# RHD2164_headstage1.net
KiCad netlist of a schematic drawn in EAGLE
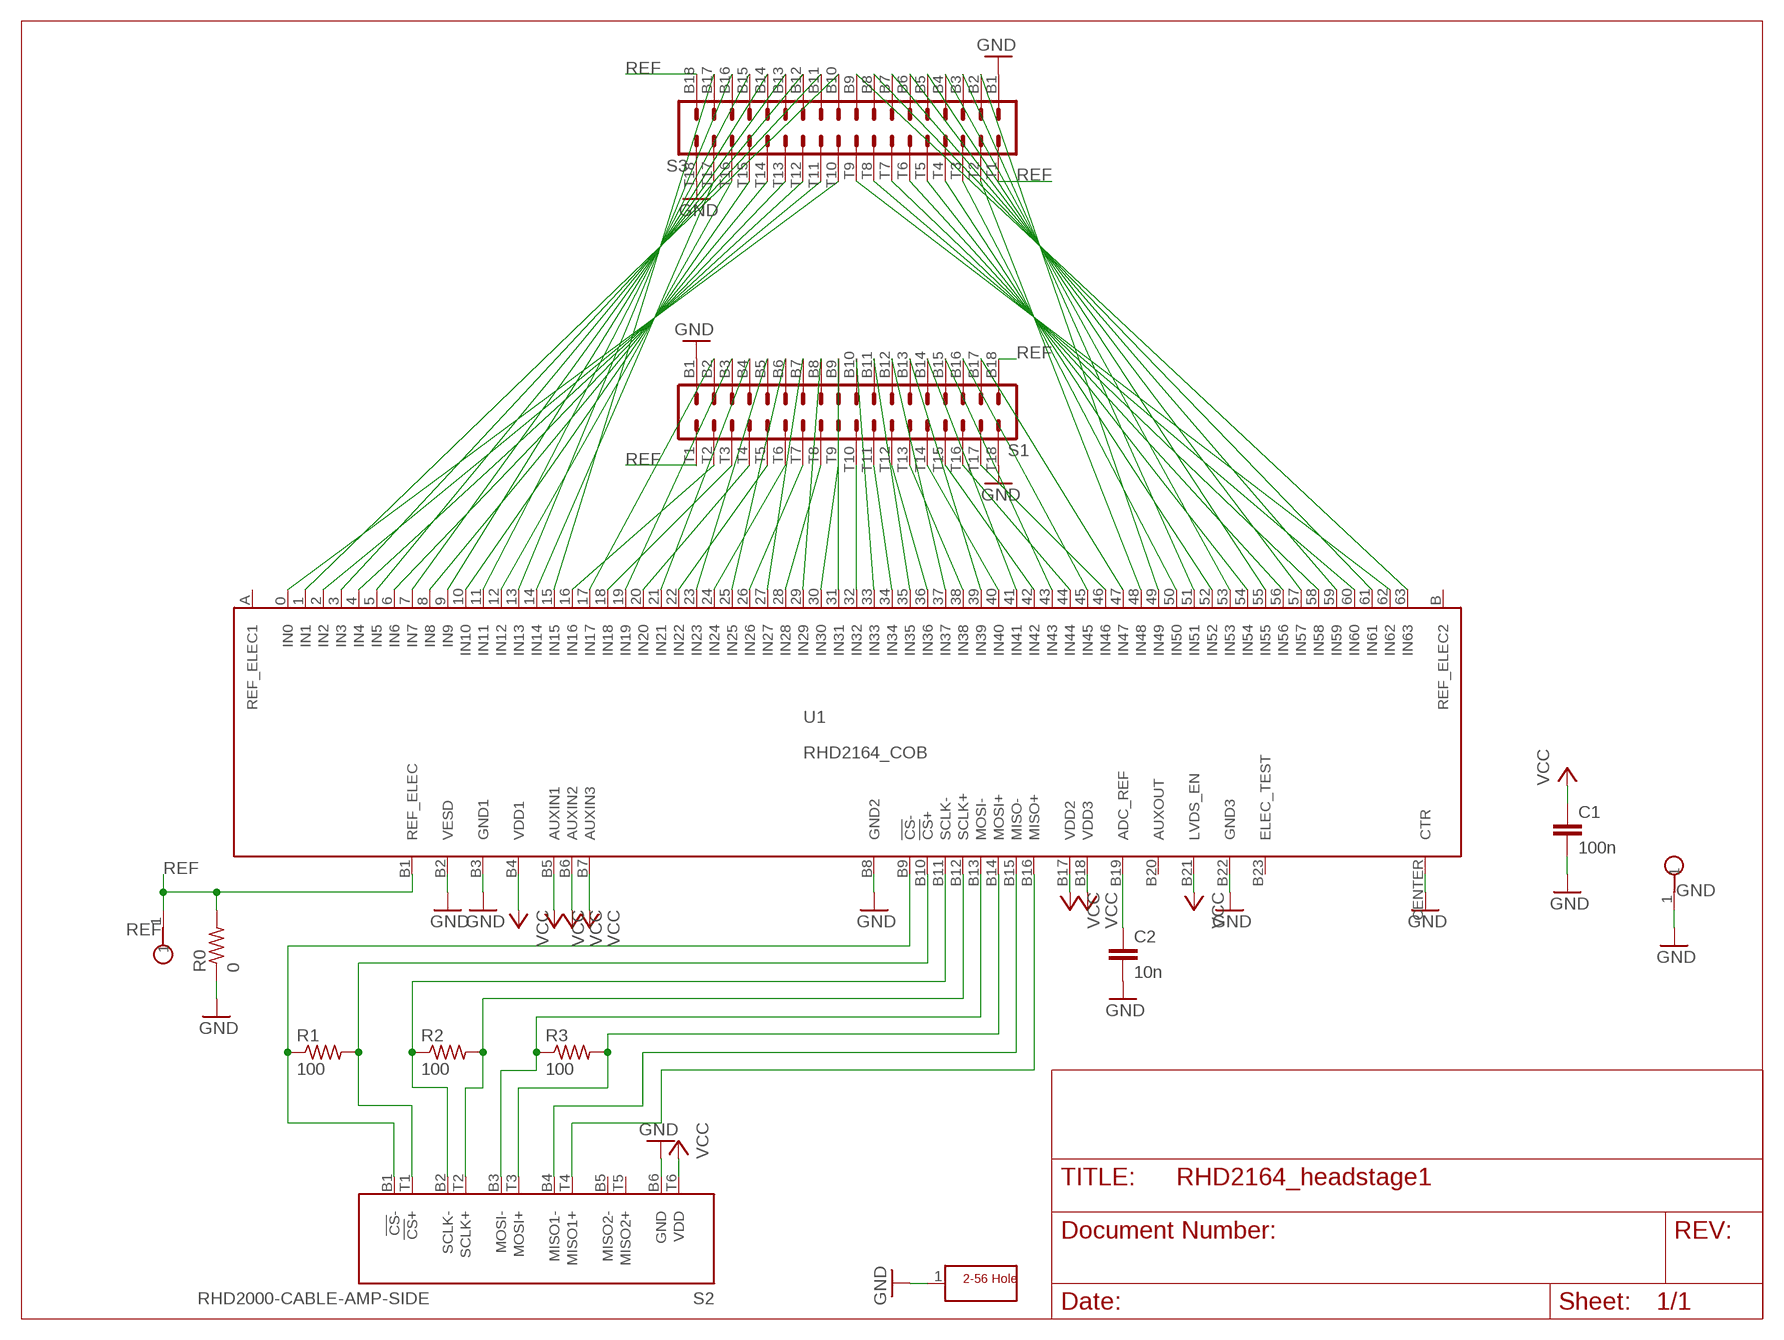
[diagram p0: schematic, sheet 1]

(export (version "E")
  (design (tool "Eeschema 10.0.6"))
  (components
    (comp (ref "C1")
      (value "100n")
      (footprint "eagle-import:0402")
      (libsource (lib "eagle-import") (part "C_0402"))
    )
    (comp (ref "C2")
      (value "10n")
      (footprint "eagle-import:0201")
      (libsource (lib "eagle-import") (part "C_0201"))
    )
    (comp (ref "GND")
      (value "TESTPOINT_SMALL")
      (footprint "eagle-import:TESTPOINT_SMALL")
      (libsource (lib "eagle-import") (part "TESTPOINT_SMALL"))
    )
    (comp (ref "H1")
      (value "SCREW_HOLE_2-56")
      (footprint "eagle-import:SCREW_HOLE_2-56")
      (libsource (lib "eagle-import") (part "SCREW_HOLE_2-56"))
    )
    (comp (ref "R0")
      (value "0")
      (footprint "eagle-import:0402")
      (libsource (lib "eagle-import") (part "R_0402"))
    )
    (comp (ref "R1")
      (value "100")
      (footprint "eagle-import:0201")
      (libsource (lib "eagle-import") (part "R_0201"))
    )
    (comp (ref "R2")
      (value "100")
      (footprint "eagle-import:0201")
      (libsource (lib "eagle-import") (part "R_0201"))
    )
    (comp (ref "R3")
      (value "100")
      (footprint "eagle-import:0201")
      (libsource (lib "eagle-import") (part "R_0201"))
    )
    (comp (ref "REF")
      (value "TESTPOINT_SMALL")
      (footprint "eagle-import:TESTPOINT_SMALL")
      (libsource (lib "eagle-import") (part "TESTPOINT_SMALL"))
    )
    (comp (ref "S1")
      (value "OMNETICS_A79025")
      (footprint "eagle-import:OMNETICS_A79025")
      (libsource (lib "eagle-import") (part "OMNETICS_A79025"))
    )
    (comp (ref "S2")
      (value "RHD2000-CABLE-AMP-SIDE")
      (footprint "eagle-import:OMNETICS_PZN-12-AA")
      (libsource (lib "eagle-import") (part "RHD2000-CABLE-AMP-SIDE"))
    )
    (comp (ref "S3")
      (value "OMNETICS_A79025")
      (footprint "eagle-import:OMNETICS_A79025")
      (libsource (lib "eagle-import") (part "OMNETICS_A79025"))
    )
    (comp (ref "U1")
      (value "RHD2164_COB")
      (footprint "eagle-import:RHD2164_COB")
      (libsource (lib "eagle-import") (part "RHD2164_COB"))
    )
  )
  (nets
    (net (code "1") (name "/REF") (class "Default")
      (node (ref "R0") (pin "2") (pinfunction "2_2") (pintype "passive"))
      (node (ref "REF") (pin "1") (pinfunction "1_1") (pintype "passive"))
      (node (ref "S1") (pin "B18") (pinfunction "B18_B18") (pintype "passive"))
      (node (ref "S1") (pin "T1") (pinfunction "T1_T1") (pintype "passive"))
      (node (ref "S3") (pin "B18") (pinfunction "B18_B18") (pintype "passive"))
      (node (ref "S3") (pin "T1") (pinfunction "T1_T1") (pintype "passive"))
      (node (ref "U1") (pin "B1") (pinfunction "REF_ELEC_B1") (pintype "input"))
    )
    (net (code "2") (name "GND") (class "Default")
      (node (ref "C1") (pin "2") (pinfunction "2_2") (pintype "passive"))
      (node (ref "C2") (pin "2") (pinfunction "2_2") (pintype "passive"))
      (node (ref "GND") (pin "1") (pinfunction "1_1") (pintype "passive"))
      (node (ref "H1") (pin "1") (pinfunction "1_1") (pintype "passive"))
      (node (ref "R0") (pin "1") (pinfunction "1_1") (pintype "passive"))
      (node (ref "S1") (pin "B1") (pinfunction "B1_B1") (pintype "passive"))
      (node (ref "S1") (pin "T18") (pinfunction "T18_T18") (pintype "passive"))
      (node (ref "S2") (pin "B6") (pinfunction "GND_B6") (pintype "power_in"))
      (node (ref "S3") (pin "B1") (pinfunction "B1_B1") (pintype "passive"))
      (node (ref "S3") (pin "T18") (pinfunction "T18_T18") (pintype "passive"))
      (node (ref "U1") (pin "B2") (pinfunction "VESD_B2") (pintype "power_in"))
      (node (ref "U1") (pin "B22") (pinfunction "GND3_B22") (pintype "power_in"))
      (node (ref "U1") (pin "B3") (pinfunction "GND1_B3") (pintype "power_in"))
      (node (ref "U1") (pin "B8") (pinfunction "GND2_B8") (pintype "power_in"))
      (node (ref "U1") (pin "CENTER") (pinfunction "CTR_CENTER") (pintype "power_in"))
    )
    (net (code "3") (name "Net-(S2-MISO1+)") (class "Default")
      (node (ref "S2") (pin "T4") (pinfunction "MISO1+_T4") (pintype "bidirectional"))
      (node (ref "U1") (pin "B16") (pinfunction "MISO+_B16") (pintype "output"))
    )
    (net (code "4") (name "Net-(S2-MISO1-)") (class "Default")
      (node (ref "S2") (pin "B4") (pinfunction "MISO1-_B4") (pintype "bidirectional"))
      (node (ref "U1") (pin "B15") (pinfunction "MISO-_B15") (pintype "output"))
    )
    (net (code "5") (name "Net-(S2-MOSI+)") (class "Default")
      (node (ref "R3") (pin "2") (pinfunction "2_2") (pintype "passive"))
      (node (ref "S2") (pin "T3") (pinfunction "MOSI+_T3") (pintype "bidirectional"))
      (node (ref "U1") (pin "B14") (pinfunction "MOSI+_B14") (pintype "input"))
    )
    (net (code "6") (name "Net-(S2-MOSI-)") (class "Default")
      (node (ref "R3") (pin "1") (pinfunction "1_1") (pintype "passive"))
      (node (ref "S2") (pin "B3") (pinfunction "MOSI-_B3") (pintype "bidirectional"))
      (node (ref "U1") (pin "B13") (pinfunction "MOSI-_B13") (pintype "input"))
    )
    (net (code "7") (name "Net-(S2-SCLK+)") (class "Default")
      (node (ref "R2") (pin "2") (pinfunction "2_2") (pintype "passive"))
      (node (ref "S2") (pin "T2") (pinfunction "SCLK+_T2") (pintype "bidirectional"))
      (node (ref "U1") (pin "B12") (pinfunction "SCLK+_B12") (pintype "input"))
    )
    (net (code "8") (name "Net-(S2-SCLK-)") (class "Default")
      (node (ref "R2") (pin "1") (pinfunction "1_1") (pintype "passive"))
      (node (ref "S2") (pin "B2") (pinfunction "SCLK-_B2") (pintype "bidirectional"))
      (node (ref "U1") (pin "B11") (pinfunction "SCLK-_B11") (pintype "input"))
    )
    (net (code "9") (name "Net-(S2-~{CS}+)") (class "Default")
      (node (ref "R1") (pin "2") (pinfunction "2_2") (pintype "passive"))
      (node (ref "S2") (pin "T1") (pinfunction "~{CS}+_T1") (pintype "bidirectional"))
      (node (ref "U1") (pin "B10") (pinfunction "~{CS}+_B10") (pintype "input"))
    )
    (net (code "10") (name "Net-(S2-~{CS}-)") (class "Default")
      (node (ref "R1") (pin "1") (pinfunction "1_1") (pintype "passive"))
      (node (ref "S2") (pin "B1") (pinfunction "~{CS}-_B1") (pintype "bidirectional"))
      (node (ref "U1") (pin "B9") (pinfunction "~{CS}-_B9") (pintype "input"))
    )
    (net (code "11") (name "Net-(U1-ADC_REF)") (class "Default")
      (node (ref "C2") (pin "1") (pinfunction "1_1") (pintype "passive"))
      (node (ref "U1") (pin "B19") (pinfunction "ADC_REF_B19") (pintype "passive"))
    )
    (net (code "12") (name "Net-(U1-IN0)") (class "Default")
      (node (ref "S3") (pin "T10") (pinfunction "T10_T10") (pintype "passive"))
      (node (ref "U1") (pin "0") (pinfunction "IN0_0") (pintype "input"))
    )
    (net (code "13") (name "Net-(U1-IN1)") (class "Default")
      (node (ref "S3") (pin "B10") (pinfunction "B10_B10") (pintype "passive"))
      (node (ref "U1") (pin "1") (pinfunction "IN1_1") (pintype "input"))
    )
    (net (code "14") (name "Net-(U1-IN2)") (class "Default")
      (node (ref "S3") (pin "T11") (pinfunction "T11_T11") (pintype "passive"))
      (node (ref "U1") (pin "2") (pinfunction "IN2_2") (pintype "input"))
    )
    (net (code "15") (name "Net-(U1-IN3)") (class "Default")
      (node (ref "S3") (pin "B11") (pinfunction "B11_B11") (pintype "passive"))
      (node (ref "U1") (pin "3") (pinfunction "IN3_3") (pintype "input"))
    )
    (net (code "16") (name "Net-(U1-IN4)") (class "Default")
      (node (ref "S3") (pin "T12") (pinfunction "T12_T12") (pintype "passive"))
      (node (ref "U1") (pin "4") (pinfunction "IN4_4") (pintype "input"))
    )
    (net (code "17") (name "Net-(U1-IN5)") (class "Default")
      (node (ref "S3") (pin "B12") (pinfunction "B12_B12") (pintype "passive"))
      (node (ref "U1") (pin "5") (pinfunction "IN5_5") (pintype "input"))
    )
    (net (code "18") (name "Net-(U1-IN6)") (class "Default")
      (node (ref "S3") (pin "T13") (pinfunction "T13_T13") (pintype "passive"))
      (node (ref "U1") (pin "6") (pinfunction "IN6_6") (pintype "input"))
    )
    (net (code "19") (name "Net-(U1-IN7)") (class "Default")
      (node (ref "S3") (pin "B13") (pinfunction "B13_B13") (pintype "passive"))
      (node (ref "U1") (pin "7") (pinfunction "IN7_7") (pintype "input"))
    )
    (net (code "20") (name "Net-(U1-IN8)") (class "Default")
      (node (ref "S3") (pin "T14") (pinfunction "T14_T14") (pintype "passive"))
      (node (ref "U1") (pin "8") (pinfunction "IN8_8") (pintype "input"))
    )
    (net (code "21") (name "Net-(U1-IN9)") (class "Default")
      (node (ref "S3") (pin "B14") (pinfunction "B14_B14") (pintype "passive"))
      (node (ref "U1") (pin "9") (pinfunction "IN9_9") (pintype "input"))
    )
    (net (code "22") (name "Net-(U1-IN10)") (class "Default")
      (node (ref "S3") (pin "T15") (pinfunction "T15_T15") (pintype "passive"))
      (node (ref "U1") (pin "10") (pinfunction "IN10_10") (pintype "input"))
    )
    (net (code "23") (name "Net-(U1-IN11)") (class "Default")
      (node (ref "S3") (pin "B15") (pinfunction "B15_B15") (pintype "passive"))
      (node (ref "U1") (pin "11") (pinfunction "IN11_11") (pintype "input"))
    )
    (net (code "24") (name "Net-(U1-IN12)") (class "Default")
      (node (ref "S3") (pin "T16") (pinfunction "T16_T16") (pintype "passive"))
      (node (ref "U1") (pin "12") (pinfunction "IN12_12") (pintype "input"))
    )
    (net (code "25") (name "Net-(U1-IN13)") (class "Default")
      (node (ref "S3") (pin "B16") (pinfunction "B16_B16") (pintype "passive"))
      (node (ref "U1") (pin "13") (pinfunction "IN13_13") (pintype "input"))
    )
    (net (code "26") (name "Net-(U1-IN14)") (class "Default")
      (node (ref "S3") (pin "T17") (pinfunction "T17_T17") (pintype "passive"))
      (node (ref "U1") (pin "14") (pinfunction "IN14_14") (pintype "input"))
    )
    (net (code "27") (name "Net-(U1-IN15)") (class "Default")
      (node (ref "S3") (pin "B17") (pinfunction "B17_B17") (pintype "passive"))
      (node (ref "U1") (pin "15") (pinfunction "IN15_15") (pintype "input"))
    )
    (net (code "28") (name "Net-(U1-IN16)") (class "Default")
      (node (ref "S1") (pin "T2") (pinfunction "T2_T2") (pintype "passive"))
      (node (ref "U1") (pin "16") (pinfunction "IN16_16") (pintype "input"))
    )
    (net (code "29") (name "Net-(U1-IN17)") (class "Default")
      (node (ref "S1") (pin "B2") (pinfunction "B2_B2") (pintype "passive"))
      (node (ref "U1") (pin "17") (pinfunction "IN17_17") (pintype "input"))
    )
    (net (code "30") (name "Net-(U1-IN18)") (class "Default")
      (node (ref "S1") (pin "T3") (pinfunction "T3_T3") (pintype "passive"))
      (node (ref "U1") (pin "18") (pinfunction "IN18_18") (pintype "input"))
    )
    (net (code "31") (name "Net-(U1-IN19)") (class "Default")
      (node (ref "S1") (pin "B3") (pinfunction "B3_B3") (pintype "passive"))
      (node (ref "U1") (pin "19") (pinfunction "IN19_19") (pintype "input"))
    )
    (net (code "32") (name "Net-(U1-IN20)") (class "Default")
      (node (ref "S1") (pin "T4") (pinfunction "T4_T4") (pintype "passive"))
      (node (ref "U1") (pin "20") (pinfunction "IN20_20") (pintype "input"))
    )
    (net (code "33") (name "Net-(U1-IN21)") (class "Default")
      (node (ref "S1") (pin "B4") (pinfunction "B4_B4") (pintype "passive"))
      (node (ref "U1") (pin "21") (pinfunction "IN21_21") (pintype "input"))
    )
    (net (code "34") (name "Net-(U1-IN22)") (class "Default")
      (node (ref "S1") (pin "T5") (pinfunction "T5_T5") (pintype "passive"))
      (node (ref "U1") (pin "22") (pinfunction "IN22_22") (pintype "input"))
    )
    (net (code "35") (name "Net-(U1-IN23)") (class "Default")
      (node (ref "S1") (pin "B5") (pinfunction "B5_B5") (pintype "passive"))
      (node (ref "U1") (pin "23") (pinfunction "IN23_23") (pintype "input"))
    )
    (net (code "36") (name "Net-(U1-IN24)") (class "Default")
      (node (ref "S1") (pin "T6") (pinfunction "T6_T6") (pintype "passive"))
      (node (ref "U1") (pin "24") (pinfunction "IN24_24") (pintype "input"))
    )
    (net (code "37") (name "Net-(U1-IN25)") (class "Default")
      (node (ref "S1") (pin "B6") (pinfunction "B6_B6") (pintype "passive"))
      (node (ref "U1") (pin "25") (pinfunction "IN25_25") (pintype "input"))
    )
    (net (code "38") (name "Net-(U1-IN26)") (class "Default")
      (node (ref "S1") (pin "T7") (pinfunction "T7_T7") (pintype "passive"))
      (node (ref "U1") (pin "26") (pinfunction "IN26_26") (pintype "input"))
    )
    (net (code "39") (name "Net-(U1-IN27)") (class "Default")
      (node (ref "S1") (pin "B7") (pinfunction "B7_B7") (pintype "passive"))
      (node (ref "U1") (pin "27") (pinfunction "IN27_27") (pintype "input"))
    )
    (net (code "40") (name "Net-(U1-IN28)") (class "Default")
      (node (ref "S1") (pin "T8") (pinfunction "T8_T8") (pintype "passive"))
      (node (ref "U1") (pin "28") (pinfunction "IN28_28") (pintype "input"))
    )
    (net (code "41") (name "Net-(U1-IN29)") (class "Default")
      (node (ref "S1") (pin "B8") (pinfunction "B8_B8") (pintype "passive"))
      (node (ref "U1") (pin "29") (pinfunction "IN29_29") (pintype "input"))
    )
    (net (code "42") (name "Net-(U1-IN30)") (class "Default")
      (node (ref "S1") (pin "T9") (pinfunction "T9_T9") (pintype "passive"))
      (node (ref "U1") (pin "30") (pinfunction "IN30_30") (pintype "input"))
    )
    (net (code "43") (name "Net-(U1-IN31)") (class "Default")
      (node (ref "S1") (pin "B9") (pinfunction "B9_B9") (pintype "passive"))
      (node (ref "U1") (pin "31") (pinfunction "IN31_31") (pintype "input"))
    )
    (net (code "44") (name "Net-(U1-IN32)") (class "Default")
      (node (ref "S1") (pin "T10") (pinfunction "T10_T10") (pintype "passive"))
      (node (ref "U1") (pin "32") (pinfunction "IN32_32") (pintype "input"))
    )
    (net (code "45") (name "Net-(U1-IN33)") (class "Default")
      (node (ref "S1") (pin "B10") (pinfunction "B10_B10") (pintype "passive"))
      (node (ref "U1") (pin "33") (pinfunction "IN33_33") (pintype "input"))
    )
    (net (code "46") (name "Net-(U1-IN34)") (class "Default")
      (node (ref "S1") (pin "T11") (pinfunction "T11_T11") (pintype "passive"))
      (node (ref "U1") (pin "34") (pinfunction "IN34_34") (pintype "input"))
    )
    (net (code "47") (name "Net-(U1-IN35)") (class "Default")
      (node (ref "S1") (pin "B11") (pinfunction "B11_B11") (pintype "passive"))
      (node (ref "U1") (pin "35") (pinfunction "IN35_35") (pintype "input"))
    )
    (net (code "48") (name "Net-(U1-IN36)") (class "Default")
      (node (ref "S1") (pin "T12") (pinfunction "T12_T12") (pintype "passive"))
      (node (ref "U1") (pin "36") (pinfunction "IN36_36") (pintype "input"))
    )
    (net (code "49") (name "Net-(U1-IN37)") (class "Default")
      (node (ref "S1") (pin "B12") (pinfunction "B12_B12") (pintype "passive"))
      (node (ref "U1") (pin "37") (pinfunction "IN37_37") (pintype "input"))
    )
    (net (code "50") (name "Net-(U1-IN38)") (class "Default")
      (node (ref "S1") (pin "T13") (pinfunction "T13_T13") (pintype "passive"))
      (node (ref "U1") (pin "38") (pinfunction "IN38_38") (pintype "input"))
    )
    (net (code "51") (name "Net-(U1-IN39)") (class "Default")
      (node (ref "S1") (pin "B13") (pinfunction "B13_B13") (pintype "passive"))
      (node (ref "U1") (pin "39") (pinfunction "IN39_39") (pintype "input"))
    )
    (net (code "52") (name "Net-(U1-IN40)") (class "Default")
      (node (ref "S1") (pin "T14") (pinfunction "T14_T14") (pintype "passive"))
      (node (ref "U1") (pin "40") (pinfunction "IN40_40") (pintype "input"))
    )
    (net (code "53") (name "Net-(U1-IN41)") (class "Default")
      (node (ref "S1") (pin "B14") (pinfunction "B14_B14") (pintype "passive"))
      (node (ref "U1") (pin "41") (pinfunction "IN41_41") (pintype "input"))
    )
    (net (code "54") (name "Net-(U1-IN42)") (class "Default")
      (node (ref "S1") (pin "T15") (pinfunction "T15_T15") (pintype "passive"))
      (node (ref "U1") (pin "42") (pinfunction "IN42_42") (pintype "input"))
    )
    (net (code "55") (name "Net-(U1-IN43)") (class "Default")
      (node (ref "S1") (pin "B15") (pinfunction "B15_B15") (pintype "passive"))
      (node (ref "U1") (pin "43") (pinfunction "IN43_43") (pintype "input"))
    )
    (net (code "56") (name "Net-(U1-IN44)") (class "Default")
      (node (ref "S1") (pin "T16") (pinfunction "T16_T16") (pintype "passive"))
      (node (ref "U1") (pin "44") (pinfunction "IN44_44") (pintype "input"))
    )
    (net (code "57") (name "Net-(U1-IN45)") (class "Default")
      (node (ref "S1") (pin "B16") (pinfunction "B16_B16") (pintype "passive"))
      (node (ref "U1") (pin "45") (pinfunction "IN45_45") (pintype "input"))
    )
    (net (code "58") (name "Net-(U1-IN46)") (class "Default")
      (node (ref "S1") (pin "T17") (pinfunction "T17_T17") (pintype "passive"))
      (node (ref "U1") (pin "46") (pinfunction "IN46_46") (pintype "input"))
    )
    (net (code "59") (name "Net-(U1-IN47)") (class "Default")
      (node (ref "S1") (pin "B17") (pinfunction "B17_B17") (pintype "passive"))
      (node (ref "U1") (pin "47") (pinfunction "IN47_47") (pintype "input"))
    )
    (net (code "60") (name "Net-(U1-IN48)") (class "Default")
      (node (ref "S3") (pin "T2") (pinfunction "T2_T2") (pintype "passive"))
      (node (ref "U1") (pin "48") (pinfunction "IN48_48") (pintype "input"))
    )
    (net (code "61") (name "Net-(U1-IN49)") (class "Default")
      (node (ref "S3") (pin "B2") (pinfunction "B2_B2") (pintype "passive"))
      (node (ref "U1") (pin "49") (pinfunction "IN49_49") (pintype "input"))
    )
    (net (code "62") (name "Net-(U1-IN50)") (class "Default")
      (node (ref "S3") (pin "T3") (pinfunction "T3_T3") (pintype "passive"))
      (node (ref "U1") (pin "50") (pinfunction "IN50_50") (pintype "input"))
    )
    (net (code "63") (name "Net-(U1-IN51)") (class "Default")
      (node (ref "S3") (pin "B3") (pinfunction "B3_B3") (pintype "passive"))
      (node (ref "U1") (pin "51") (pinfunction "IN51_51") (pintype "input"))
    )
    (net (code "64") (name "Net-(U1-IN52)") (class "Default")
      (node (ref "S3") (pin "T4") (pinfunction "T4_T4") (pintype "passive"))
      (node (ref "U1") (pin "52") (pinfunction "IN52_52") (pintype "input"))
    )
    (net (code "65") (name "Net-(U1-IN53)") (class "Default")
      (node (ref "S3") (pin "B4") (pinfunction "B4_B4") (pintype "passive"))
      (node (ref "U1") (pin "53") (pinfunction "IN53_53") (pintype "input"))
    )
    (net (code "66") (name "Net-(U1-IN54)") (class "Default")
      (node (ref "S3") (pin "T5") (pinfunction "T5_T5") (pintype "passive"))
      (node (ref "U1") (pin "54") (pinfunction "IN54_54") (pintype "input"))
    )
    (net (code "67") (name "Net-(U1-IN55)") (class "Default")
      (node (ref "S3") (pin "B5") (pinfunction "B5_B5") (pintype "passive"))
      (node (ref "U1") (pin "55") (pinfunction "IN55_55") (pintype "input"))
    )
    (net (code "68") (name "Net-(U1-IN56)") (class "Default")
      (node (ref "S3") (pin "T6") (pinfunction "T6_T6") (pintype "passive"))
      (node (ref "U1") (pin "56") (pinfunction "IN56_56") (pintype "input"))
    )
    (net (code "69") (name "Net-(U1-IN57)") (class "Default")
      (node (ref "S3") (pin "B6") (pinfunction "B6_B6") (pintype "passive"))
      (node (ref "U1") (pin "57") (pinfunction "IN57_57") (pintype "input"))
    )
    (net (code "70") (name "Net-(U1-IN58)") (class "Default")
      (node (ref "S3") (pin "T7") (pinfunction "T7_T7") (pintype "passive"))
      (node (ref "U1") (pin "58") (pinfunction "IN58_58") (pintype "input"))
    )
    (net (code "71") (name "Net-(U1-IN59)") (class "Default")
      (node (ref "S3") (pin "B7") (pinfunction "B7_B7") (pintype "passive"))
      (node (ref "U1") (pin "59") (pinfunction "IN59_59") (pintype "input"))
    )
    (net (code "72") (name "Net-(U1-IN60)") (class "Default")
      (node (ref "S3") (pin "T8") (pinfunction "T8_T8") (pintype "passive"))
      (node (ref "U1") (pin "60") (pinfunction "IN60_60") (pintype "input"))
    )
    (net (code "73") (name "Net-(U1-IN61)") (class "Default")
      (node (ref "S3") (pin "B8") (pinfunction "B8_B8") (pintype "passive"))
      (node (ref "U1") (pin "61") (pinfunction "IN61_61") (pintype "input"))
    )
    (net (code "74") (name "Net-(U1-IN62)") (class "Default")
      (node (ref "S3") (pin "T9") (pinfunction "T9_T9") (pintype "passive"))
      (node (ref "U1") (pin "62") (pinfunction "IN62_62") (pintype "input"))
    )
    (net (code "75") (name "Net-(U1-IN63)") (class "Default")
      (node (ref "S3") (pin "B9") (pinfunction "B9_B9") (pintype "passive"))
      (node (ref "U1") (pin "63") (pinfunction "IN63_63") (pintype "input"))
    )
    (net (code "76") (name "VCC") (class "Default")
      (node (ref "C1") (pin "1") (pinfunction "1_1") (pintype "passive"))
      (node (ref "S2") (pin "T6") (pinfunction "VDD_T6") (pintype "bidirectional"))
      (node (ref "U1") (pin "B17") (pinfunction "VDD2_B17") (pintype "power_in"))
      (node (ref "U1") (pin "B18") (pinfunction "VDD3_B18") (pintype "power_in"))
      (node (ref "U1") (pin "B21") (pinfunction "LVDS_EN_B21") (pintype "input"))
      (node (ref "U1") (pin "B4") (pinfunction "VDD1_B4") (pintype "power_in"))
      (node (ref "U1") (pin "B5") (pinfunction "AUXIN1_B5") (pintype "input"))
      (node (ref "U1") (pin "B6") (pinfunction "AUXIN2_B6") (pintype "input"))
      (node (ref "U1") (pin "B7") (pinfunction "AUXIN3_B7") (pintype "input"))
    )
    (net (code "77") (name "unconnected-(S2-MISO2+-PadT5)") (class "Default")
      (node (ref "S2") (pin "T5") (pinfunction "MISO2+_T5") (pintype "bidirectional"))
    )
    (net (code "78") (name "unconnected-(S2-MISO2--PadB5)") (class "Default")
      (node (ref "S2") (pin "B5") (pinfunction "MISO2-_B5") (pintype "bidirectional"))
    )
    (net (code "79") (name "unconnected-(U1-AUXOUT-PadB20)") (class "Default")
      (node (ref "U1") (pin "B20") (pinfunction "AUXOUT_B20") (pintype "tri_state"))
    )
    (net (code "80") (name "unconnected-(U1-ELEC_TEST-PadB23)") (class "Default")
      (node (ref "U1") (pin "B23") (pinfunction "ELEC_TEST_B23") (pintype "input"))
    )
    (net (code "81") (name "unconnected-(U1-REF_ELEC1-PadA)") (class "Default")
      (node (ref "U1") (pin "A") (pinfunction "REF_ELEC1_A") (pintype "input"))
    )
    (net (code "82") (name "unconnected-(U1-REF_ELEC2-PadB)") (class "Default")
      (node (ref "U1") (pin "B") (pinfunction "REF_ELEC2_B") (pintype "input"))
    )
  )
)
